# sch_ma_pro_easyeda.net
KiCad netlist of a schematic drawn in EasyEDA
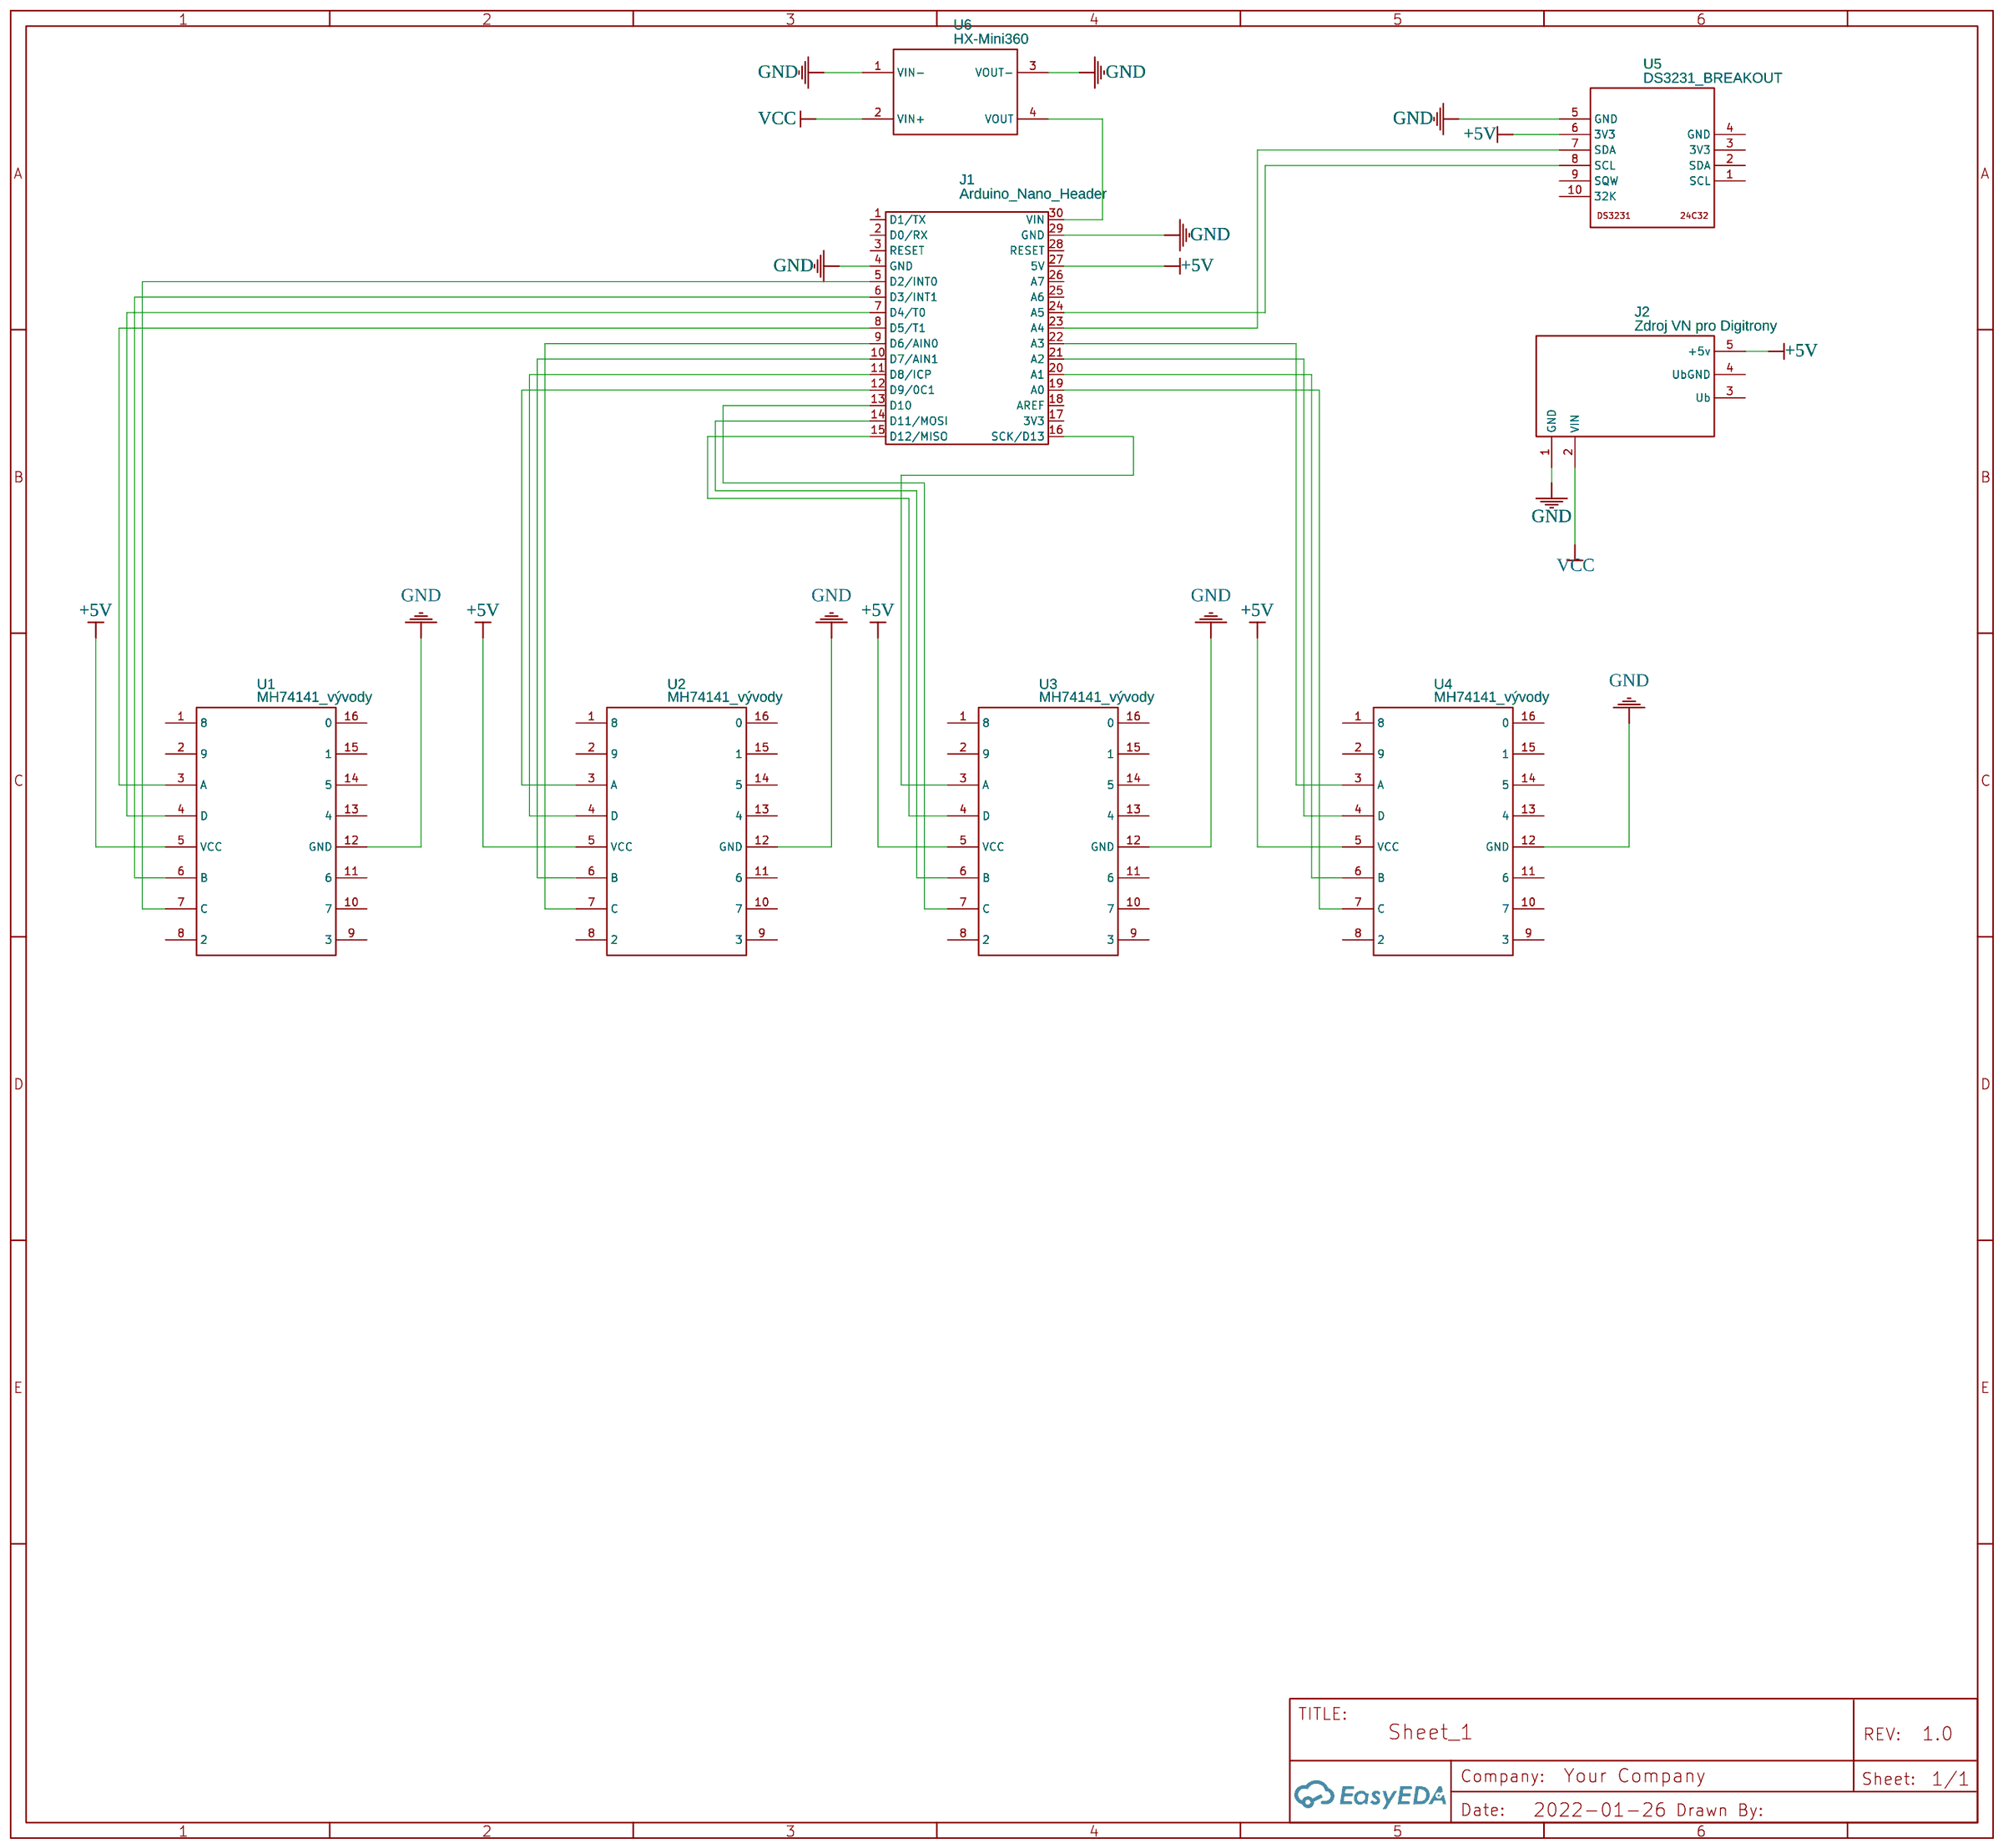
[diagram p0: schematic sheet]

(export (version "E")
  (design (tool "Eeschema 10.0.6"))
  (components
    (comp (ref "J1") (value "Arduino_Nano_Header") (libsource (lib "") (part "Arduino_Nano_Header")))
    (comp (ref "J2") (value "Zdroj VN pro Digitrony") (libsource (lib "") (part "Zdroj VN pro Digitrony")))
    (comp (ref "U1") (value "MH74141_vývody") (libsource (lib "") (part "MH74141_vývody")))
    (comp (ref "U2") (value "MH74141_vývody") (libsource (lib "") (part "MH74141_vývody")))
    (comp (ref "U3") (value "MH74141_vývody") (libsource (lib "") (part "MH74141_vývody")))
    (comp (ref "U4") (value "MH74141_vývody") (libsource (lib "") (part "MH74141_vývody")))
    (comp (ref "U5")
      (value "DS3231_BREAKOUT")
      (fields (field (name "BOM_Supplier Part") "undefined"))
      (libsource (lib "") (part "DS3231_BREAKOUT"))
    )
    (comp (ref "U6") (value "HX-Mini360") (libsource (lib "") (part "HX-Mini360")))
  )
  (nets
    (net (code "1") (name "+5V") (class "Default")
      (node (ref "J1") (pin "27") (pinfunction "5V_27") (pintype "unspecified"))
      (node (ref "J2") (pin "5") (pinfunction "+5v_5") (pintype "passive"))
      (node (ref "U1") (pin "5") (pinfunction "VCC_5") (pintype "passive"))
      (node (ref "U2") (pin "5") (pinfunction "VCC_5") (pintype "passive"))
      (node (ref "U3") (pin "5") (pinfunction "VCC_5") (pintype "passive"))
      (node (ref "U4") (pin "5") (pinfunction "VCC_5") (pintype "passive"))
      (node (ref "U5") (pin "6") (pinfunction "3V3_6") (pintype "unspecified"))
    )
    (net (code "2") (name "GND") (class "Default")
      (node (ref "J1") (pin "29") (pinfunction "GND_29") (pintype "unspecified"))
      (node (ref "J1") (pin "4") (pinfunction "GND_4") (pintype "unspecified"))
      (node (ref "J2") (pin "1") (pinfunction "GND_1") (pintype "passive"))
      (node (ref "U1") (pin "12") (pinfunction "GND_12") (pintype "passive"))
      (node (ref "U2") (pin "12") (pinfunction "GND_12") (pintype "passive"))
      (node (ref "U3") (pin "12") (pinfunction "GND_12") (pintype "passive"))
      (node (ref "U4") (pin "12") (pinfunction "GND_12") (pintype "passive"))
      (node (ref "U5") (pin "5") (pinfunction "GND_5") (pintype "unspecified"))
      (node (ref "U6") (pin "1") (pinfunction "VIN-_1") (pintype "input"))
      (node (ref "U6") (pin "3") (pinfunction "VOUT-_3") (pintype "output"))
    )
    (net (code "3") (name "Net-(J1-A0)") (class "Default")
      (node (ref "J1") (pin "19") (pinfunction "A0_19") (pintype "unspecified"))
      (node (ref "U4") (pin "7") (pinfunction "C_7") (pintype "input"))
    )
    (net (code "4") (name "Net-(J1-A1)") (class "Default")
      (node (ref "J1") (pin "20") (pinfunction "A1_20") (pintype "unspecified"))
      (node (ref "U4") (pin "6") (pinfunction "B_6") (pintype "input"))
    )
    (net (code "5") (name "Net-(J1-A2)") (class "Default")
      (node (ref "J1") (pin "21") (pinfunction "A2_21") (pintype "unspecified"))
      (node (ref "U4") (pin "4") (pinfunction "D_4") (pintype "input"))
    )
    (net (code "6") (name "Net-(J1-A3)") (class "Default")
      (node (ref "J1") (pin "22") (pinfunction "A3_22") (pintype "unspecified"))
      (node (ref "U4") (pin "3") (pinfunction "A_3") (pintype "input"))
    )
    (net (code "7") (name "Net-(J1-A4)") (class "Default")
      (node (ref "J1") (pin "23") (pinfunction "A4_23") (pintype "unspecified"))
      (node (ref "U5") (pin "7") (pinfunction "SDA_7") (pintype "unspecified"))
    )
    (net (code "8") (name "Net-(J1-A5)") (class "Default")
      (node (ref "J1") (pin "24") (pinfunction "A5_24") (pintype "unspecified"))
      (node (ref "U5") (pin "8") (pinfunction "SCL_8") (pintype "unspecified"))
    )
    (net (code "9") (name "Net-(J1-D2{slash}INT0)") (class "Default")
      (node (ref "J1") (pin "5") (pinfunction "D2/INT0_5") (pintype "unspecified"))
      (node (ref "U1") (pin "7") (pinfunction "C_7") (pintype "input"))
    )
    (net (code "10") (name "Net-(J1-D3{slash}INT1)") (class "Default")
      (node (ref "J1") (pin "6") (pinfunction "D3/INT1_6") (pintype "unspecified"))
      (node (ref "U1") (pin "6") (pinfunction "B_6") (pintype "input"))
    )
    (net (code "11") (name "Net-(J1-D4{slash}T0)") (class "Default")
      (node (ref "J1") (pin "7") (pinfunction "D4/T0_7") (pintype "unspecified"))
      (node (ref "U1") (pin "4") (pinfunction "D_4") (pintype "input"))
    )
    (net (code "12") (name "Net-(J1-D5{slash}T1)") (class "Default")
      (node (ref "J1") (pin "8") (pinfunction "D5/T1_8") (pintype "unspecified"))
      (node (ref "U1") (pin "3") (pinfunction "A_3") (pintype "input"))
    )
    (net (code "13") (name "Net-(J1-D6{slash}AIN0)") (class "Default")
      (node (ref "J1") (pin "9") (pinfunction "D6/AIN0_9") (pintype "unspecified"))
      (node (ref "U2") (pin "7") (pinfunction "C_7") (pintype "input"))
    )
    (net (code "14") (name "Net-(J1-D7{slash}AIN1)") (class "Default")
      (node (ref "J1") (pin "10") (pinfunction "D7/AIN1_10") (pintype "unspecified"))
      (node (ref "U2") (pin "6") (pinfunction "B_6") (pintype "input"))
    )
    (net (code "15") (name "Net-(J1-D8{slash}ICP)") (class "Default")
      (node (ref "J1") (pin "11") (pinfunction "D8/ICP_11") (pintype "unspecified"))
      (node (ref "U2") (pin "4") (pinfunction "D_4") (pintype "input"))
    )
    (net (code "16") (name "Net-(J1-D9{slash}0C1)") (class "Default")
      (node (ref "J1") (pin "12") (pinfunction "D9/0C1_12") (pintype "unspecified"))
      (node (ref "U2") (pin "3") (pinfunction "A_3") (pintype "input"))
    )
    (net (code "17") (name "Net-(J1-D10)") (class "Default")
      (node (ref "J1") (pin "13") (pinfunction "D10_13") (pintype "unspecified"))
      (node (ref "U3") (pin "7") (pinfunction "C_7") (pintype "input"))
    )
    (net (code "18") (name "Net-(J1-D11{slash}MOSI)") (class "Default")
      (node (ref "J1") (pin "14") (pinfunction "D11/MOSI_14") (pintype "unspecified"))
      (node (ref "U3") (pin "6") (pinfunction "B_6") (pintype "input"))
    )
    (net (code "19") (name "Net-(J1-D12{slash}MISO)") (class "Default")
      (node (ref "J1") (pin "15") (pinfunction "D12/MISO_15") (pintype "unspecified"))
      (node (ref "U3") (pin "4") (pinfunction "D_4") (pintype "input"))
    )
    (net (code "20") (name "Net-(J1-SCK{slash}D13)") (class "Default")
      (node (ref "J1") (pin "16") (pinfunction "SCK/D13_16") (pintype "unspecified"))
      (node (ref "U3") (pin "3") (pinfunction "A_3") (pintype "input"))
    )
    (net (code "21") (name "Net-(J1-VIN)") (class "Default")
      (node (ref "J1") (pin "30") (pinfunction "VIN_30") (pintype "unspecified"))
      (node (ref "U6") (pin "4") (pinfunction "VOUT_4") (pintype "output"))
    )
    (net (code "22") (name "VCC") (class "Default")
      (node (ref "J2") (pin "2") (pinfunction "VIN_2") (pintype "passive"))
      (node (ref "U6") (pin "2") (pinfunction "VIN+_2") (pintype "input"))
    )
    (net (code "23") (name "unconnected-(J1-3V3-Pad17)") (class "Default")
      (node (ref "J1") (pin "17") (pinfunction "3V3_17") (pintype "unspecified"))
    )
    (net (code "24") (name "unconnected-(J1-A6-Pad25)") (class "Default")
      (node (ref "J1") (pin "25") (pinfunction "A6_25") (pintype "unspecified"))
    )
    (net (code "25") (name "unconnected-(J1-A7-Pad26)") (class "Default")
      (node (ref "J1") (pin "26") (pinfunction "A7_26") (pintype "unspecified"))
    )
    (net (code "26") (name "unconnected-(J1-AREF-Pad18)") (class "Default")
      (node (ref "J1") (pin "18") (pinfunction "AREF_18") (pintype "unspecified"))
    )
    (net (code "27") (name "unconnected-(J1-D0{slash}RX-Pad2)") (class "Default")
      (node (ref "J1") (pin "2") (pinfunction "D0/RX_2") (pintype "unspecified"))
    )
    (net (code "28") (name "unconnected-(J1-D1{slash}TX-Pad1)") (class "Default")
      (node (ref "J1") (pin "1") (pinfunction "D1/TX_1") (pintype "unspecified"))
    )
    (net (code "29") (name "unconnected-(J1-RESET-Pad3)") (class "Default")
      (node (ref "J1") (pin "3") (pinfunction "RESET_3") (pintype "unspecified"))
    )
    (net (code "30") (name "unconnected-(J1-RESET-Pad28)") (class "Default")
      (node (ref "J1") (pin "28") (pinfunction "RESET_28") (pintype "unspecified"))
    )
    (net (code "31") (name "unconnected-(J2-Ub-Pad3)") (class "Default")
      (node (ref "J2") (pin "3") (pinfunction "Ub_3") (pintype "passive"))
    )
    (net (code "32") (name "unconnected-(J2-UbGND-Pad4)") (class "Default")
      (node (ref "J2") (pin "4") (pinfunction "UbGND_4") (pintype "passive"))
    )
    (net (code "33") (name "unconnected-(U1-0-Pad16)") (class "Default")
      (node (ref "U1") (pin "16") (pinfunction "0_16") (pintype "output"))
    )
    (net (code "34") (name "unconnected-(U1-1-Pad15)") (class "Default")
      (node (ref "U1") (pin "15") (pinfunction "1_15") (pintype "output"))
    )
    (net (code "35") (name "unconnected-(U1-2-Pad8)") (class "Default")
      (node (ref "U1") (pin "8") (pinfunction "2_8") (pintype "output"))
    )
    (net (code "36") (name "unconnected-(U1-3-Pad9)") (class "Default")
      (node (ref "U1") (pin "9") (pinfunction "3_9") (pintype "output"))
    )
    (net (code "37") (name "unconnected-(U1-4-Pad13)") (class "Default")
      (node (ref "U1") (pin "13") (pinfunction "4_13") (pintype "output"))
    )
    (net (code "38") (name "unconnected-(U1-5-Pad14)") (class "Default")
      (node (ref "U1") (pin "14") (pinfunction "5_14") (pintype "output"))
    )
    (net (code "39") (name "unconnected-(U1-6-Pad11)") (class "Default")
      (node (ref "U1") (pin "11") (pinfunction "6_11") (pintype "output"))
    )
    (net (code "40") (name "unconnected-(U1-7-Pad10)") (class "Default")
      (node (ref "U1") (pin "10") (pinfunction "7_10") (pintype "output"))
    )
    (net (code "41") (name "unconnected-(U1-8-Pad1)") (class "Default")
      (node (ref "U1") (pin "1") (pinfunction "8_1") (pintype "output"))
    )
    (net (code "42") (name "unconnected-(U1-9-Pad2)") (class "Default")
      (node (ref "U1") (pin "2") (pinfunction "9_2") (pintype "output"))
    )
    (net (code "43") (name "unconnected-(U2-0-Pad16)") (class "Default")
      (node (ref "U2") (pin "16") (pinfunction "0_16") (pintype "output"))
    )
    (net (code "44") (name "unconnected-(U2-1-Pad15)") (class "Default")
      (node (ref "U2") (pin "15") (pinfunction "1_15") (pintype "output"))
    )
    (net (code "45") (name "unconnected-(U2-2-Pad8)") (class "Default")
      (node (ref "U2") (pin "8") (pinfunction "2_8") (pintype "output"))
    )
    (net (code "46") (name "unconnected-(U2-3-Pad9)") (class "Default")
      (node (ref "U2") (pin "9") (pinfunction "3_9") (pintype "output"))
    )
    (net (code "47") (name "unconnected-(U2-4-Pad13)") (class "Default")
      (node (ref "U2") (pin "13") (pinfunction "4_13") (pintype "output"))
    )
    (net (code "48") (name "unconnected-(U2-5-Pad14)") (class "Default")
      (node (ref "U2") (pin "14") (pinfunction "5_14") (pintype "output"))
    )
    (net (code "49") (name "unconnected-(U2-6-Pad11)") (class "Default")
      (node (ref "U2") (pin "11") (pinfunction "6_11") (pintype "output"))
    )
    (net (code "50") (name "unconnected-(U2-7-Pad10)") (class "Default")
      (node (ref "U2") (pin "10") (pinfunction "7_10") (pintype "output"))
    )
    (net (code "51") (name "unconnected-(U2-8-Pad1)") (class "Default")
      (node (ref "U2") (pin "1") (pinfunction "8_1") (pintype "output"))
    )
    (net (code "52") (name "unconnected-(U2-9-Pad2)") (class "Default")
      (node (ref "U2") (pin "2") (pinfunction "9_2") (pintype "output"))
    )
    (net (code "53") (name "unconnected-(U3-0-Pad16)") (class "Default")
      (node (ref "U3") (pin "16") (pinfunction "0_16") (pintype "output"))
    )
    (net (code "54") (name "unconnected-(U3-1-Pad15)") (class "Default")
      (node (ref "U3") (pin "15") (pinfunction "1_15") (pintype "output"))
    )
    (net (code "55") (name "unconnected-(U3-2-Pad8)") (class "Default")
      (node (ref "U3") (pin "8") (pinfunction "2_8") (pintype "output"))
    )
    (net (code "56") (name "unconnected-(U3-3-Pad9)") (class "Default")
      (node (ref "U3") (pin "9") (pinfunction "3_9") (pintype "output"))
    )
    (net (code "57") (name "unconnected-(U3-4-Pad13)") (class "Default")
      (node (ref "U3") (pin "13") (pinfunction "4_13") (pintype "output"))
    )
    (net (code "58") (name "unconnected-(U3-5-Pad14)") (class "Default")
      (node (ref "U3") (pin "14") (pinfunction "5_14") (pintype "output"))
    )
    (net (code "59") (name "unconnected-(U3-6-Pad11)") (class "Default")
      (node (ref "U3") (pin "11") (pinfunction "6_11") (pintype "output"))
    )
    (net (code "60") (name "unconnected-(U3-7-Pad10)") (class "Default")
      (node (ref "U3") (pin "10") (pinfunction "7_10") (pintype "output"))
    )
    (net (code "61") (name "unconnected-(U3-8-Pad1)") (class "Default")
      (node (ref "U3") (pin "1") (pinfunction "8_1") (pintype "output"))
    )
    (net (code "62") (name "unconnected-(U3-9-Pad2)") (class "Default")
      (node (ref "U3") (pin "2") (pinfunction "9_2") (pintype "output"))
    )
    (net (code "63") (name "unconnected-(U4-0-Pad16)") (class "Default")
      (node (ref "U4") (pin "16") (pinfunction "0_16") (pintype "output"))
    )
    (net (code "64") (name "unconnected-(U4-1-Pad15)") (class "Default")
      (node (ref "U4") (pin "15") (pinfunction "1_15") (pintype "output"))
    )
    (net (code "65") (name "unconnected-(U4-2-Pad8)") (class "Default")
      (node (ref "U4") (pin "8") (pinfunction "2_8") (pintype "output"))
    )
    (net (code "66") (name "unconnected-(U4-3-Pad9)") (class "Default")
      (node (ref "U4") (pin "9") (pinfunction "3_9") (pintype "output"))
    )
    (net (code "67") (name "unconnected-(U4-4-Pad13)") (class "Default")
      (node (ref "U4") (pin "13") (pinfunction "4_13") (pintype "output"))
    )
    (net (code "68") (name "unconnected-(U4-5-Pad14)") (class "Default")
      (node (ref "U4") (pin "14") (pinfunction "5_14") (pintype "output"))
    )
    (net (code "69") (name "unconnected-(U4-6-Pad11)") (class "Default")
      (node (ref "U4") (pin "11") (pinfunction "6_11") (pintype "output"))
    )
    (net (code "70") (name "unconnected-(U4-7-Pad10)") (class "Default")
      (node (ref "U4") (pin "10") (pinfunction "7_10") (pintype "output"))
    )
    (net (code "71") (name "unconnected-(U4-8-Pad1)") (class "Default")
      (node (ref "U4") (pin "1") (pinfunction "8_1") (pintype "output"))
    )
    (net (code "72") (name "unconnected-(U4-9-Pad2)") (class "Default")
      (node (ref "U4") (pin "2") (pinfunction "9_2") (pintype "output"))
    )
    (net (code "73") (name "unconnected-(U5-3V3-Pad3)") (class "Default")
      (node (ref "U5") (pin "3") (pinfunction "3V3_3") (pintype "unspecified"))
    )
    (net (code "74") (name "unconnected-(U5-32K-Pad10)") (class "Default")
      (node (ref "U5") (pin "10") (pinfunction "32K_10") (pintype "unspecified"))
    )
    (net (code "75") (name "unconnected-(U5-GND-Pad4)") (class "Default")
      (node (ref "U5") (pin "4") (pinfunction "GND_4") (pintype "unspecified"))
    )
    (net (code "76") (name "unconnected-(U5-SCL-Pad1)") (class "Default")
      (node (ref "U5") (pin "1") (pinfunction "SCL_1") (pintype "unspecified"))
    )
    (net (code "77") (name "unconnected-(U5-SDA-Pad2)") (class "Default")
      (node (ref "U5") (pin "2") (pinfunction "SDA_2") (pintype "unspecified"))
    )
    (net (code "78") (name "unconnected-(U5-SQW-Pad9)") (class "Default")
      (node (ref "U5") (pin "9") (pinfunction "SQW_9") (pintype "unspecified"))
    )
  )
)
